# OSIVE_IMS.net
KiCad netlist of a schematic drawn in EAGLE
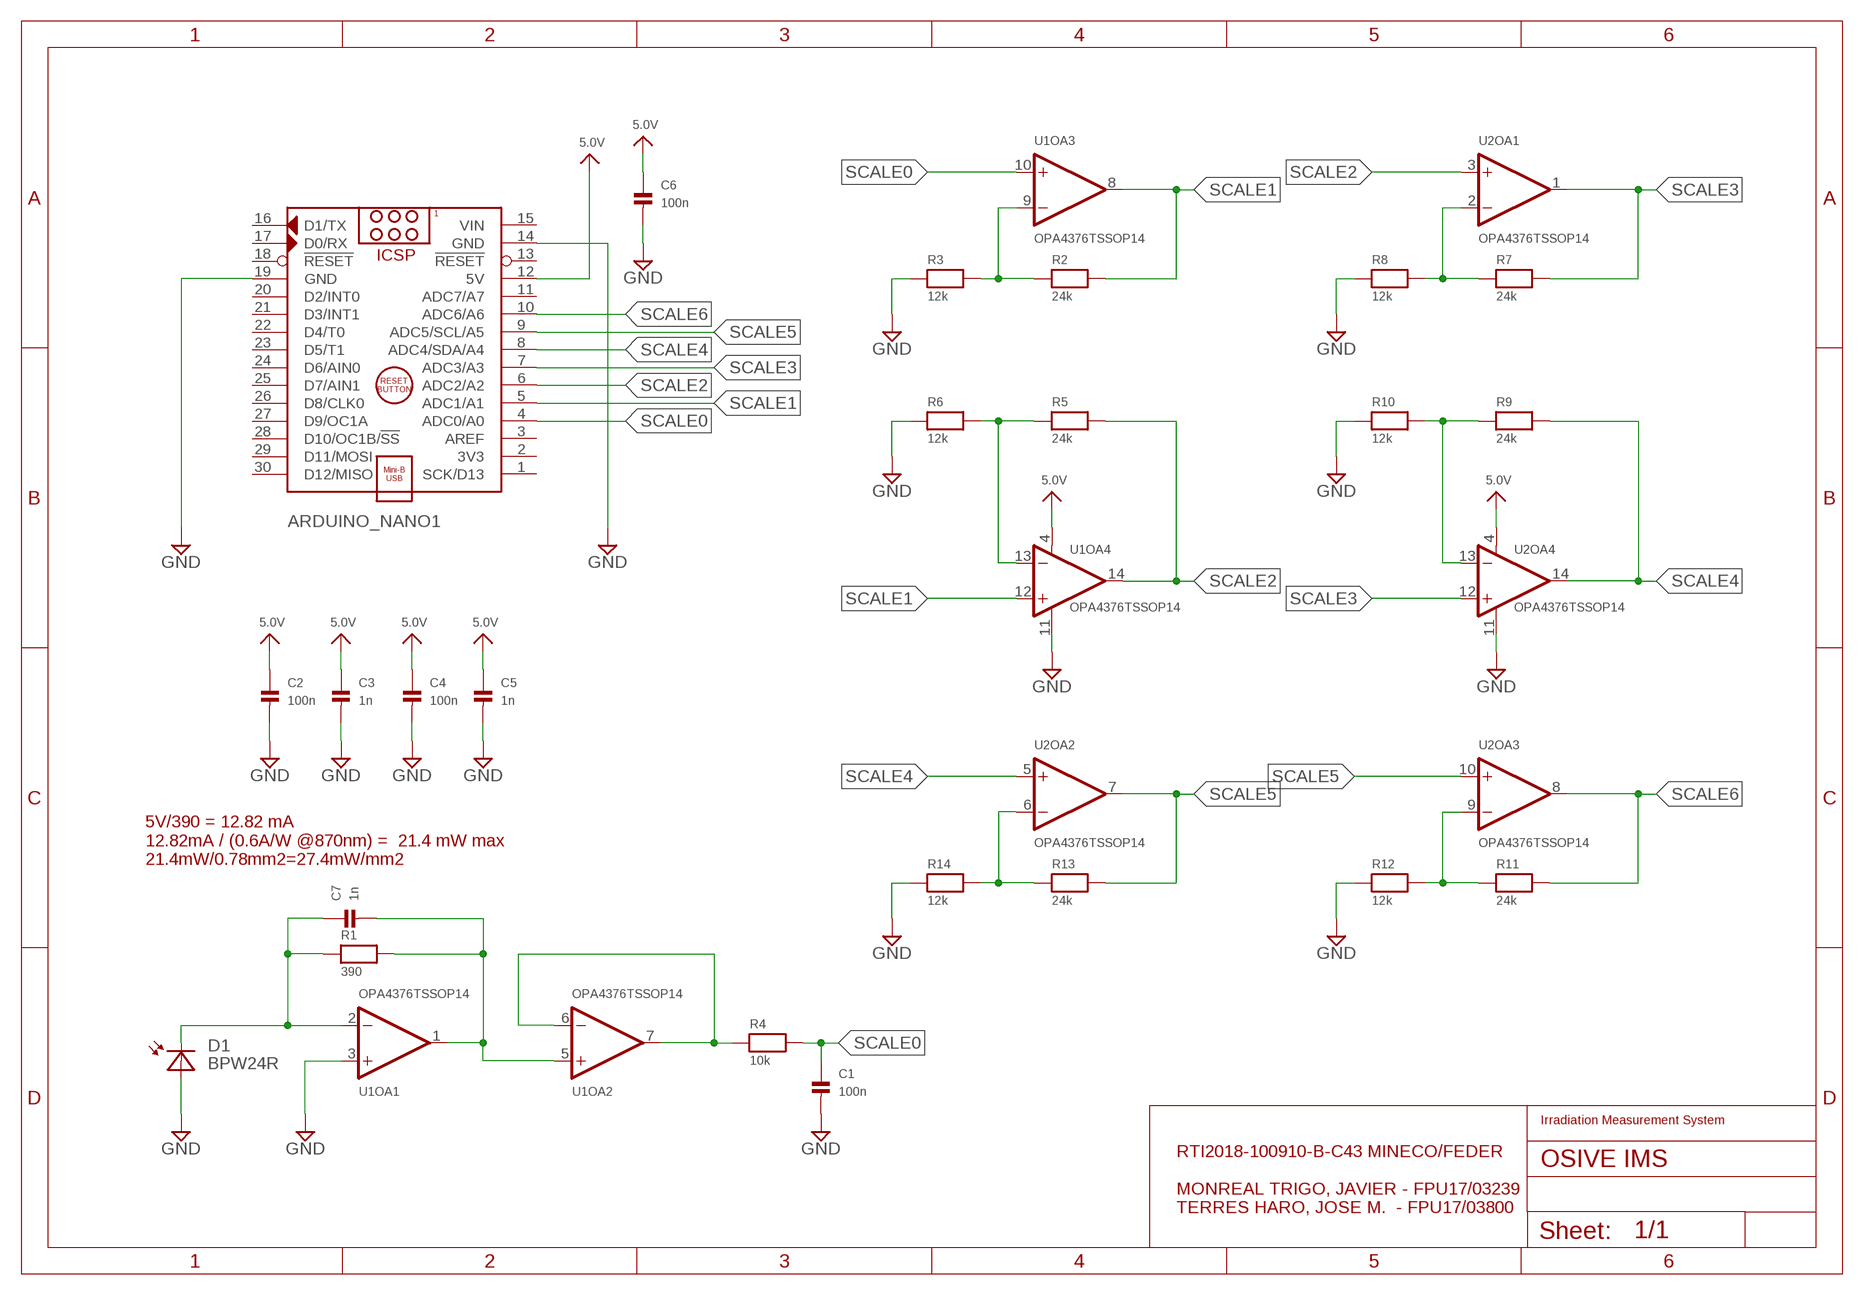
[diagram p0: schematic, sheet 1]

(export (version "E")
  (design (tool "Eeschema 10.0.6"))
  (components
    (comp (ref "ARDUINO_NANO1")
      (value "ARDUINO_NANO")
      (footprint "eagle-import:ARDUINO_NANO")
      (libsource (lib "eagle-import") (part "ARDUINO_NANO"))
    )
    (comp (ref "C1")
      (value "100n")
      (footprint "eagle-import:0805")
      (libsource (lib "eagle-import") (part "CAP_CERAMIC0805"))
    )
    (comp (ref "C2")
      (value "100n")
      (footprint "eagle-import:0805")
      (libsource (lib "eagle-import") (part "CAP_CERAMIC0805"))
    )
    (comp (ref "C3")
      (value "1n")
      (footprint "eagle-import:0805")
      (libsource (lib "eagle-import") (part "CAP_CERAMIC0805"))
    )
    (comp (ref "C4")
      (value "100n")
      (footprint "eagle-import:0805")
      (libsource (lib "eagle-import") (part "CAP_CERAMIC0805"))
    )
    (comp (ref "C5")
      (value "1n")
      (footprint "eagle-import:0805")
      (libsource (lib "eagle-import") (part "CAP_CERAMIC0805"))
    )
    (comp (ref "C6")
      (value "100n")
      (footprint "eagle-import:0805")
      (libsource (lib "eagle-import") (part "CAP_CERAMIC0805"))
    )
    (comp (ref "C7")
      (value "1n")
      (footprint "eagle-import:0805")
      (libsource (lib "eagle-import") (part "CAP_CERAMIC0805"))
    )
    (comp (ref "D1")
      (value "BPW24R")
      (footprint "eagle-import:TO-18")
      (libsource (lib "eagle-import") (part "BPW24R"))
    )
    (comp (ref "R1")
      (value "390")
      (footprint "eagle-import:0805")
      (libsource (lib "eagle-import") (part "RESISTOR0805"))
    )
    (comp (ref "R2")
      (value "24k")
      (footprint "eagle-import:0805")
      (libsource (lib "eagle-import") (part "RESISTOR0805"))
    )
    (comp (ref "R3")
      (value "12k")
      (footprint "eagle-import:0805")
      (libsource (lib "eagle-import") (part "RESISTOR0805"))
    )
    (comp (ref "R4")
      (value "10k")
      (footprint "eagle-import:0805")
      (libsource (lib "eagle-import") (part "RESISTOR0805"))
    )
    (comp (ref "R5")
      (value "24k")
      (footprint "eagle-import:0805")
      (libsource (lib "eagle-import") (part "RESISTOR0805"))
    )
    (comp (ref "R6")
      (value "12k")
      (footprint "eagle-import:0805")
      (libsource (lib "eagle-import") (part "RESISTOR0805"))
    )
    (comp (ref "R7")
      (value "24k")
      (footprint "eagle-import:0805")
      (libsource (lib "eagle-import") (part "RESISTOR0805"))
    )
    (comp (ref "R8")
      (value "12k")
      (footprint "eagle-import:0805")
      (libsource (lib "eagle-import") (part "RESISTOR0805"))
    )
    (comp (ref "R9")
      (value "24k")
      (footprint "eagle-import:0805")
      (libsource (lib "eagle-import") (part "RESISTOR0805"))
    )
    (comp (ref "R10")
      (value "12k")
      (footprint "eagle-import:0805")
      (libsource (lib "eagle-import") (part "RESISTOR0805"))
    )
    (comp (ref "R11")
      (value "24k")
      (footprint "eagle-import:0805")
      (libsource (lib "eagle-import") (part "RESISTOR0805"))
    )
    (comp (ref "R12")
      (value "12k")
      (footprint "eagle-import:0805")
      (libsource (lib "eagle-import") (part "RESISTOR0805"))
    )
    (comp (ref "R13")
      (value "24k")
      (footprint "eagle-import:0805")
      (libsource (lib "eagle-import") (part "RESISTOR0805"))
    )
    (comp (ref "R14")
      (value "12k")
      (footprint "eagle-import:0805")
      (libsource (lib "eagle-import") (part "RESISTOR0805"))
    )
    (comp (ref "U1")
      (value "OPA4376TSSOP14")
      (footprint "eagle-import:TSSOP14-NOTHERMALPAD")
      (libsource (lib "eagle-import") (part "OPA4376TSSOP14"))
    )
    (comp (ref "U2")
      (value "OPA4376TSSOP14")
      (footprint "eagle-import:TSSOP14-NOTHERMALPAD")
      (libsource (lib "eagle-import") (part "OPA4376TSSOP14"))
    )
  )
  (nets
    (net (code "1") (name "/VIN") (class "Default")
      (node (ref "ARDUINO_NANO1") (pin "15") (pinfunction "VIN_15") (pintype "power_in"))
    )
    (net (code "2") (name "5.0V") (class "Default")
      (node (ref "ARDUINO_NANO1") (pin "12") (pinfunction "5V_12") (pintype "power_in"))
      (node (ref "C2") (pin "1") (pinfunction "P$1_1") (pintype "passive"))
      (node (ref "C3") (pin "1") (pinfunction "P$1_1") (pintype "passive"))
      (node (ref "C4") (pin "1") (pinfunction "P$1_1") (pintype "passive"))
      (node (ref "C5") (pin "1") (pinfunction "P$1_1") (pintype "passive"))
      (node (ref "C6") (pin "1") (pinfunction "P$1_1") (pintype "passive"))
      (node (ref "U1") (pin "4") (pinfunction "V+_4") (pintype "power_in"))
      (node (ref "U2") (pin "4") (pinfunction "V+_4") (pintype "power_in"))
    )
    (net (code "3") (name "GND") (class "Default")
      (node (ref "ARDUINO_NANO1") (pin "14") (pinfunction "GND_14") (pintype "power_in"))
      (node (ref "ARDUINO_NANO1") (pin "19") (pinfunction "GND_19") (pintype "power_in"))
      (node (ref "C1") (pin "2") (pinfunction "P$2_2") (pintype "passive"))
      (node (ref "C2") (pin "2") (pinfunction "P$2_2") (pintype "passive"))
      (node (ref "C3") (pin "2") (pinfunction "P$2_2") (pintype "passive"))
      (node (ref "C4") (pin "2") (pinfunction "P$2_2") (pintype "passive"))
      (node (ref "C5") (pin "2") (pinfunction "P$2_2") (pintype "passive"))
      (node (ref "C6") (pin "2") (pinfunction "P$2_2") (pintype "passive"))
      (node (ref "D1") (pin "A") (pinfunction "A_A") (pintype "passive"))
      (node (ref "R10") (pin "1") (pinfunction "1_1") (pintype "passive"))
      (node (ref "R12") (pin "1") (pinfunction "1_1") (pintype "passive"))
      (node (ref "R14") (pin "1") (pinfunction "1_1") (pintype "passive"))
      (node (ref "R3") (pin "1") (pinfunction "1_1") (pintype "passive"))
      (node (ref "R6") (pin "1") (pinfunction "1_1") (pintype "passive"))
      (node (ref "R8") (pin "1") (pinfunction "1_1") (pintype "passive"))
      (node (ref "U1") (pin "11") (pinfunction "V-_11") (pintype "power_in"))
      (node (ref "U1") (pin "3") (pinfunction "+IN_3") (pintype "input"))
      (node (ref "U2") (pin "11") (pinfunction "V-_11") (pintype "power_in"))
    )
    (net (code "4") (name "Net-(C7-P$1)") (class "Default")
      (node (ref "C7") (pin "1") (pinfunction "P$1_1") (pintype "passive"))
      (node (ref "D1") (pin "K") (pinfunction "C_K") (pintype "passive"))
      (node (ref "R1") (pin "1") (pinfunction "1_1") (pintype "passive"))
      (node (ref "U1") (pin "2") (pinfunction "-IN_2") (pintype "input"))
    )
    (net (code "5") (name "Net-(C7-P$2)") (class "Default")
      (node (ref "C7") (pin "2") (pinfunction "P$2_2") (pintype "passive"))
      (node (ref "R1") (pin "2") (pinfunction "2_2") (pintype "passive"))
      (node (ref "U1") (pin "1") (pinfunction "OUT_1") (pintype "output"))
      (node (ref "U1") (pin "5") (pinfunction "+IN_5") (pintype "input"))
    )
    (net (code "6") (name "Net-(U1B--IN)") (class "Default")
      (node (ref "R4") (pin "1") (pinfunction "1_1") (pintype "passive"))
      (node (ref "U1") (pin "6") (pinfunction "-IN_6") (pintype "input"))
      (node (ref "U1") (pin "7") (pinfunction "OUT_7") (pintype "output"))
    )
    (net (code "7") (name "Net-(U1C--IN)") (class "Default")
      (node (ref "R2") (pin "1") (pinfunction "1_1") (pintype "passive"))
      (node (ref "R3") (pin "2") (pinfunction "2_2") (pintype "passive"))
      (node (ref "U1") (pin "9") (pinfunction "-IN_9") (pintype "input"))
    )
    (net (code "8") (name "Net-(U1D--IN)") (class "Default")
      (node (ref "R5") (pin "1") (pinfunction "1_1") (pintype "passive"))
      (node (ref "R6") (pin "2") (pinfunction "2_2") (pintype "passive"))
      (node (ref "U1") (pin "13") (pinfunction "-IN_13") (pintype "input"))
    )
    (net (code "9") (name "Net-(U2A--IN)") (class "Default")
      (node (ref "R7") (pin "1") (pinfunction "1_1") (pintype "passive"))
      (node (ref "R8") (pin "2") (pinfunction "2_2") (pintype "passive"))
      (node (ref "U2") (pin "2") (pinfunction "-IN_2") (pintype "input"))
    )
    (net (code "10") (name "Net-(U2B--IN)") (class "Default")
      (node (ref "R13") (pin "1") (pinfunction "1_1") (pintype "passive"))
      (node (ref "R14") (pin "2") (pinfunction "2_2") (pintype "passive"))
      (node (ref "U2") (pin "6") (pinfunction "-IN_6") (pintype "input"))
    )
    (net (code "11") (name "Net-(U2C--IN)") (class "Default")
      (node (ref "R11") (pin "1") (pinfunction "1_1") (pintype "passive"))
      (node (ref "R12") (pin "2") (pinfunction "2_2") (pintype "passive"))
      (node (ref "U2") (pin "9") (pinfunction "-IN_9") (pintype "input"))
    )
    (net (code "12") (name "Net-(U2D--IN)") (class "Default")
      (node (ref "R10") (pin "2") (pinfunction "2_2") (pintype "passive"))
      (node (ref "R9") (pin "1") (pinfunction "1_1") (pintype "passive"))
      (node (ref "U2") (pin "13") (pinfunction "-IN_13") (pintype "input"))
    )
    (net (code "13") (name "SCALE0") (class "Default")
      (node (ref "ARDUINO_NANO1") (pin "4") (pinfunction "ADC0/A0_4") (pintype "bidirectional"))
      (node (ref "C1") (pin "1") (pinfunction "P$1_1") (pintype "passive"))
      (node (ref "R4") (pin "2") (pinfunction "2_2") (pintype "passive"))
      (node (ref "U1") (pin "10") (pinfunction "+IN_10") (pintype "input"))
    )
    (net (code "14") (name "SCALE1") (class "Default")
      (node (ref "ARDUINO_NANO1") (pin "5") (pinfunction "ADC1/A1_5") (pintype "bidirectional"))
      (node (ref "R2") (pin "2") (pinfunction "2_2") (pintype "passive"))
      (node (ref "U1") (pin "12") (pinfunction "+IN_12") (pintype "input"))
      (node (ref "U1") (pin "8") (pinfunction "OUT_8") (pintype "output"))
    )
    (net (code "15") (name "SCALE2") (class "Default")
      (node (ref "ARDUINO_NANO1") (pin "6") (pinfunction "ADC2/A2_6") (pintype "bidirectional"))
      (node (ref "R5") (pin "2") (pinfunction "2_2") (pintype "passive"))
      (node (ref "U1") (pin "14") (pinfunction "OUT_14") (pintype "output"))
      (node (ref "U2") (pin "3") (pinfunction "+IN_3") (pintype "input"))
    )
    (net (code "16") (name "SCALE3") (class "Default")
      (node (ref "ARDUINO_NANO1") (pin "7") (pinfunction "ADC3/A3_7") (pintype "bidirectional"))
      (node (ref "R7") (pin "2") (pinfunction "2_2") (pintype "passive"))
      (node (ref "U2") (pin "1") (pinfunction "OUT_1") (pintype "output"))
      (node (ref "U2") (pin "12") (pinfunction "+IN_12") (pintype "input"))
    )
    (net (code "17") (name "SCALE4") (class "Default")
      (node (ref "ARDUINO_NANO1") (pin "8") (pinfunction "ADC4/SDA/A4_8") (pintype "bidirectional"))
      (node (ref "R9") (pin "2") (pinfunction "2_2") (pintype "passive"))
      (node (ref "U2") (pin "14") (pinfunction "OUT_14") (pintype "output"))
      (node (ref "U2") (pin "5") (pinfunction "+IN_5") (pintype "input"))
    )
    (net (code "18") (name "SCALE5") (class "Default")
      (node (ref "ARDUINO_NANO1") (pin "9") (pinfunction "ADC5/SCL/A5_9") (pintype "bidirectional"))
      (node (ref "R13") (pin "2") (pinfunction "2_2") (pintype "passive"))
      (node (ref "U2") (pin "10") (pinfunction "+IN_10") (pintype "input"))
      (node (ref "U2") (pin "7") (pinfunction "OUT_7") (pintype "output"))
    )
    (net (code "19") (name "SCALE6") (class "Default")
      (node (ref "ARDUINO_NANO1") (pin "10") (pinfunction "ADC6/A6_10") (pintype "bidirectional"))
      (node (ref "R11") (pin "2") (pinfunction "2_2") (pintype "passive"))
      (node (ref "U2") (pin "8") (pinfunction "OUT_8") (pintype "output"))
    )
    (net (code "20") (name "unconnected-(ARDUINO_NANO1-3V3-Pad2)") (class "Default")
      (node (ref "ARDUINO_NANO1") (pin "2") (pinfunction "3V3_2") (pintype "output"))
    )
    (net (code "21") (name "unconnected-(ARDUINO_NANO1-ADC7{slash}A7-Pad11)") (class "Default")
      (node (ref "ARDUINO_NANO1") (pin "11") (pinfunction "ADC7/A7_11") (pintype "bidirectional"))
    )
    (net (code "22") (name "unconnected-(ARDUINO_NANO1-AREF-Pad3)") (class "Default")
      (node (ref "ARDUINO_NANO1") (pin "3") (pinfunction "AREF_3") (pintype "input"))
    )
    (net (code "23") (name "unconnected-(ARDUINO_NANO1-D0{slash}RX-Pad17)") (class "Default")
      (node (ref "ARDUINO_NANO1") (pin "17") (pinfunction "D0/RX_17") (pintype "bidirectional"))
    )
    (net (code "24") (name "unconnected-(ARDUINO_NANO1-D1{slash}TX-Pad16)") (class "Default")
      (node (ref "ARDUINO_NANO1") (pin "16") (pinfunction "D1/TX_16") (pintype "bidirectional"))
    )
    (net (code "25") (name "unconnected-(ARDUINO_NANO1-D2{slash}INT0-Pad20)") (class "Default")
      (node (ref "ARDUINO_NANO1") (pin "20") (pinfunction "D2/INT0_20") (pintype "bidirectional"))
    )
    (net (code "26") (name "unconnected-(ARDUINO_NANO1-D3{slash}INT1-Pad21)") (class "Default")
      (node (ref "ARDUINO_NANO1") (pin "21") (pinfunction "D3/INT1_21") (pintype "bidirectional"))
    )
    (net (code "27") (name "unconnected-(ARDUINO_NANO1-D4{slash}T0-Pad22)") (class "Default")
      (node (ref "ARDUINO_NANO1") (pin "22") (pinfunction "D4/T0_22") (pintype "bidirectional"))
    )
    (net (code "28") (name "unconnected-(ARDUINO_NANO1-D5{slash}T1-Pad23)") (class "Default")
      (node (ref "ARDUINO_NANO1") (pin "23") (pinfunction "D5/T1_23") (pintype "bidirectional"))
    )
    (net (code "29") (name "unconnected-(ARDUINO_NANO1-D6{slash}AIN0-Pad24)") (class "Default")
      (node (ref "ARDUINO_NANO1") (pin "24") (pinfunction "D6/AIN0_24") (pintype "bidirectional"))
    )
    (net (code "30") (name "unconnected-(ARDUINO_NANO1-D7{slash}AIN1-Pad25)") (class "Default")
      (node (ref "ARDUINO_NANO1") (pin "25") (pinfunction "D7/AIN1_25") (pintype "bidirectional"))
    )
    (net (code "31") (name "unconnected-(ARDUINO_NANO1-D8{slash}CLK0-Pad26)") (class "Default")
      (node (ref "ARDUINO_NANO1") (pin "26") (pinfunction "D8/CLK0_26") (pintype "bidirectional"))
    )
    (net (code "32") (name "unconnected-(ARDUINO_NANO1-D9{slash}OC1A-Pad27)") (class "Default")
      (node (ref "ARDUINO_NANO1") (pin "27") (pinfunction "D9/OC1A_27") (pintype "bidirectional"))
    )
    (net (code "33") (name "unconnected-(ARDUINO_NANO1-D10{slash}OC1B{slash}~{SS}-Pad28)") (class "Default")
      (node (ref "ARDUINO_NANO1") (pin "28") (pinfunction "D10/OC1B/~{SS}_28") (pintype "bidirectional"))
    )
    (net (code "34") (name "unconnected-(ARDUINO_NANO1-D11{slash}MOSI-Pad29)") (class "Default")
      (node (ref "ARDUINO_NANO1") (pin "29") (pinfunction "D11/MOSI_29") (pintype "bidirectional"))
    )
    (net (code "35") (name "unconnected-(ARDUINO_NANO1-D12{slash}MISO-Pad30)") (class "Default")
      (node (ref "ARDUINO_NANO1") (pin "30") (pinfunction "D12/MISO_30") (pintype "bidirectional"))
    )
    (net (code "36") (name "unconnected-(ARDUINO_NANO1-SCK{slash}D13-Pad1)") (class "Default")
      (node (ref "ARDUINO_NANO1") (pin "1") (pinfunction "SCK/D13_1") (pintype "bidirectional"))
    )
    (net (code "37") (name "unconnected-(ARDUINO_NANO1-~{RESET}-Pad13)") (class "Default")
      (node (ref "ARDUINO_NANO1") (pin "13") (pinfunction "~{RESET}_13") (pintype "input"))
    )
    (net (code "38") (name "unconnected-(ARDUINO_NANO1-~{RESET}-Pad18)") (class "Default")
      (node (ref "ARDUINO_NANO1") (pin "18") (pinfunction "~{RESET}_18") (pintype "input"))
    )
  )
)
